# rev0_1.net
KiCad netlist of a schematic drawn in EAGLE
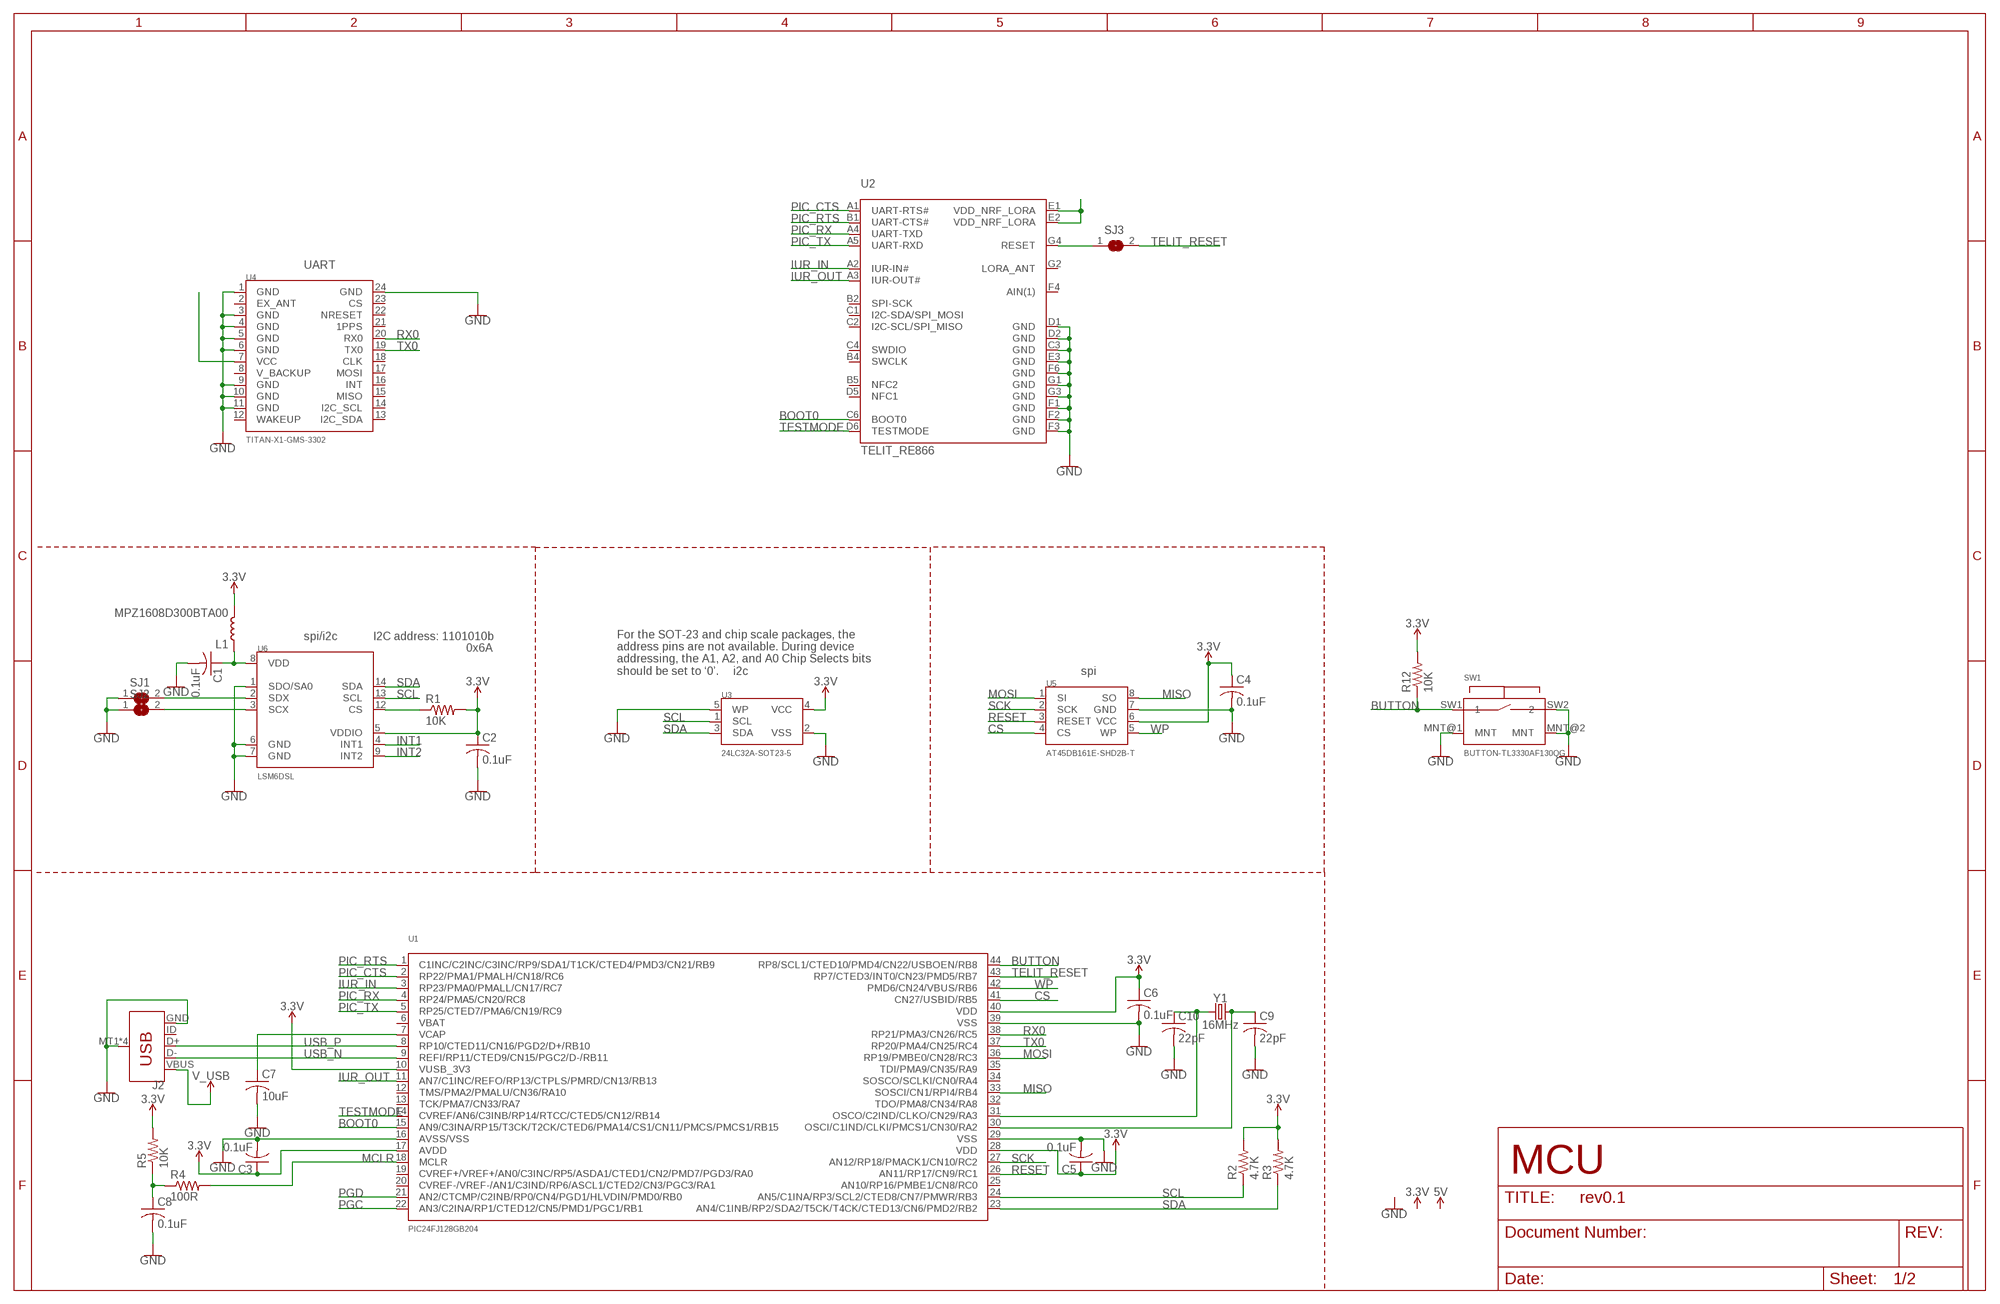
[diagram p0: schematic, sheet 1]
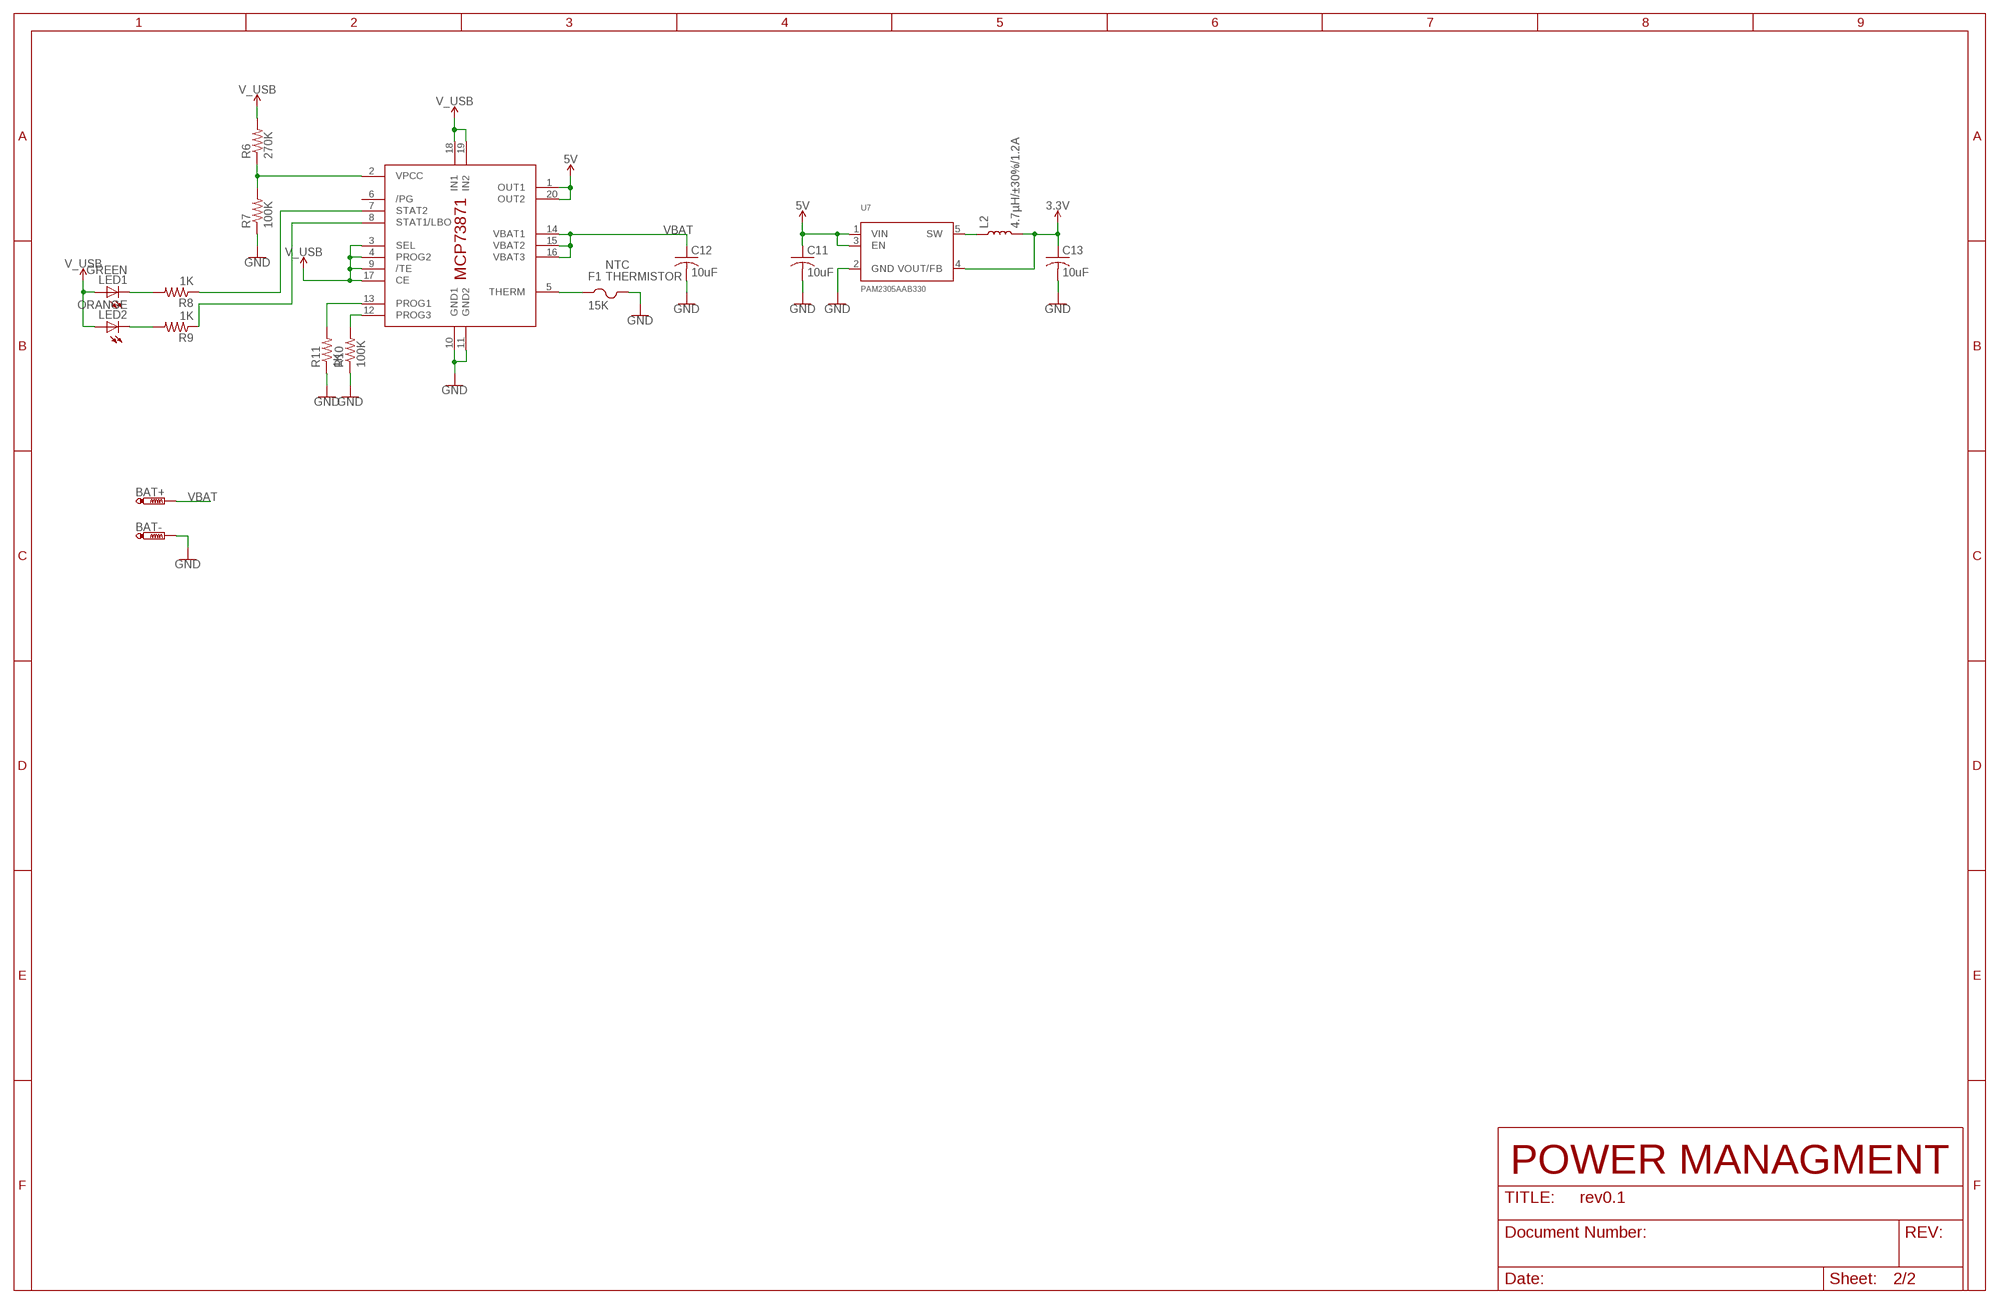
[diagram p1: schematic, sheet 2]

(export (version "E")
  (design (tool "Eeschema 10.0.6"))
  (components
    (comp (ref "C1")
      (value "0.1uF")
      (footprint "eagle-import:C0402")
      (libsource (lib "eagle-import") (part "C-USC0402"))
    )
    (comp (ref "C2")
      (value "0.1uF")
      (footprint "eagle-import:C0402")
      (libsource (lib "eagle-import") (part "C-USC0402"))
    )
    (comp (ref "C3")
      (value "0.1uF")
      (footprint "eagle-import:C0402")
      (libsource (lib "eagle-import") (part "C-USC0402"))
    )
    (comp (ref "C4")
      (value "0.1uF")
      (footprint "eagle-import:C0402")
      (libsource (lib "eagle-import") (part "C-USC0402"))
    )
    (comp (ref "C5")
      (value "0.1uF")
      (footprint "eagle-import:C0402")
      (libsource (lib "eagle-import") (part "C-USC0402"))
    )
    (comp (ref "C6")
      (value "0.1uF")
      (footprint "eagle-import:C0402")
      (libsource (lib "eagle-import") (part "C-USC0402"))
    )
    (comp (ref "C7")
      (value "10uF")
      (footprint "eagle-import:C0603")
      (libsource (lib "eagle-import") (part "C-USC0603"))
    )
    (comp (ref "C8")
      (value "0.1uF")
      (footprint "eagle-import:C0402")
      (libsource (lib "eagle-import") (part "C-USC0402"))
    )
    (comp (ref "C9")
      (value "22pF")
      (footprint "eagle-import:C0402")
      (libsource (lib "eagle-import") (part "C-USC0402"))
    )
    (comp (ref "C10")
      (value "22pF")
      (footprint "eagle-import:C0402")
      (libsource (lib "eagle-import") (part "C-USC0402"))
    )
    (comp (ref "J2")
      (value "USB_MICRO-B_SMT")
      (footprint "eagle-import:USB-MICROB")
      (libsource (lib "eagle-import") (part "USB_MICRO-B_SMT"))
    )
    (comp (ref "L1")
      (value "MPZ1608D300BTA00")
      (footprint "eagle-import:0402")
      (libsource (lib "eagle-import") (part "INDUCTOR-0402-3.9NH"))
    )
    (comp (ref "R1")
      (value "10K")
      (footprint "eagle-import:R0402")
      (libsource (lib "eagle-import") (part "R-US_R0402"))
    )
    (comp (ref "R2")
      (value "4.7K")
      (footprint "eagle-import:R0402")
      (libsource (lib "eagle-import") (part "R-US_R0402"))
    )
    (comp (ref "R3")
      (value "4.7K")
      (footprint "eagle-import:R0402")
      (libsource (lib "eagle-import") (part "R-US_R0402"))
    )
    (comp (ref "R4")
      (value "100R")
      (footprint "eagle-import:R0402")
      (libsource (lib "eagle-import") (part "R-US_R0402"))
    )
    (comp (ref "R5")
      (value "10K")
      (footprint "eagle-import:R0402")
      (libsource (lib "eagle-import") (part "R-US_R0402"))
    )
    (comp (ref "R12")
      (value "10K")
      (footprint "eagle-import:R0402")
      (libsource (lib "eagle-import") (part "R-US_R0402"))
    )
    (comp (ref "SJ1") (value "SJ") (footprint "eagle-import:SJ") (libsource (lib "eagle-import") (part "SJ")))
    (comp (ref "SJ2") (value "SJ") (footprint "eagle-import:SJ") (libsource (lib "eagle-import") (part "SJ")))
    (comp (ref "SJ3") (value "SJ") (footprint "eagle-import:SJ") (libsource (lib "eagle-import") (part "SJ")))
    (comp (ref "SW1")
      (value "BUTTON-TL3330AF130QG")
      (footprint "eagle-import:BUTTON-TL3330AF130QG")
      (libsource (lib "eagle-import") (part "BUTTON-TL3330AF130QG"))
    )
    (comp (ref "U1")
      (value "PIC24FJ128GB204")
      (footprint "eagle-import:PIC24FJ128GB204")
      (libsource (lib "eagle-import") (part "PIC24FJ128GB204"))
    )
    (comp (ref "U2")
      (value "TELIT_RE866")
      (footprint "eagle-import:TELIT_RE866")
      (libsource (lib "eagle-import") (part "TELIT_RE866"))
    )
    (comp (ref "U3")
      (value "24LC32A-SOT23-5")
      (footprint "eagle-import:24LC32A-SOT23-5")
      (libsource (lib "eagle-import") (part "24LC32A-SOT23-5"))
    )
    (comp (ref "U4")
      (value "TITAN-X1-GMS-3302")
      (footprint "eagle-import:TITAN-X1-GMS-3302")
      (libsource (lib "eagle-import") (part "TITAN-X1-GMS-3302"))
    )
    (comp (ref "U5")
      (value "AT45DB161E-SHD2B-T")
      (footprint "eagle-import:AT45DB161E-SHD2B-T")
      (libsource (lib "eagle-import") (part "AT45DB161E-SHD2B-T"))
    )
    (comp (ref "U6")
      (value "LSM6DSL")
      (footprint "eagle-import:LSM6DSL")
      (fields (field (name "SPICEPREFIX") "X"))
      (libsource (lib "eagle-import") (part "LSM6DSL"))
    )
    (comp (ref "Y1")
      (value "16MHz")
      (footprint "eagle-import:CRYSTAL-SMD-5X3.2-4PAD")
      (libsource (lib "eagle-import") (part "CRYSTAL-16MHZSMD-5X3.2"))
    )
    (comp (ref "BAT+")
      (value "PTR1B2,54")
      (footprint "eagle-import:B2,54")
      (libsource (lib "eagle-import") (part "PTR1B2,54"))
    )
    (comp (ref "BAT-")
      (value "PTR1B2,54")
      (footprint "eagle-import:B2,54")
      (libsource (lib "eagle-import") (part "PTR1B2,54"))
    )
    (comp (ref "C11")
      (value "10uF")
      (footprint "eagle-import:C0805")
      (libsource (lib "eagle-import") (part "C-USC0805"))
    )
    (comp (ref "C12")
      (value "10uF")
      (footprint "eagle-import:C0603")
      (libsource (lib "eagle-import") (part "C-USC0603"))
    )
    (comp (ref "C13")
      (value "10uF")
      (footprint "eagle-import:C0805")
      (libsource (lib "eagle-import") (part "C-USC0805"))
    )
    (comp (ref "F1")
      (value "15K")
      (footprint "eagle-import:R1206")
      (libsource (lib "eagle-import") (part "PTCFUSE-1206"))
    )
    (comp (ref "IC2")
      (value "MCP73871")
      (footprint "eagle-import:QFN20")
      (libsource (lib "eagle-import") (part "MCP73871"))
    )
    (comp (ref "L2")
      (value "4.7µH/±30%/1.2A")
      (footprint "eagle-import:INDUCTOR_4.7UH")
      (libsource (lib "eagle-import") (part "INDUCTOR-CDRH-4.7UH"))
    )
    (comp (ref "LED1")
      (value "GREEN")
      (footprint "eagle-import:CHIP-LED0603")
      (libsource (lib "eagle-import") (part "LEDCHIP-LED0603"))
    )
    (comp (ref "LED2")
      (value "ORANGE")
      (footprint "eagle-import:CHIP-LED0603")
      (libsource (lib "eagle-import") (part "LEDCHIP-LED0603"))
    )
    (comp (ref "R6")
      (value "270K")
      (footprint "eagle-import:R0402")
      (libsource (lib "eagle-import") (part "R-US_R0402"))
    )
    (comp (ref "R7")
      (value "100K")
      (footprint "eagle-import:R0402")
      (libsource (lib "eagle-import") (part "R-US_R0402"))
    )
    (comp (ref "R8")
      (value "1K")
      (footprint "eagle-import:R0402")
      (libsource (lib "eagle-import") (part "R-US_R0402"))
    )
    (comp (ref "R9")
      (value "1K")
      (footprint "eagle-import:R0402")
      (libsource (lib "eagle-import") (part "R-US_R0402"))
    )
    (comp (ref "R10")
      (value "100K")
      (footprint "eagle-import:R0402")
      (libsource (lib "eagle-import") (part "R-US_R0402"))
    )
    (comp (ref "R11")
      (value "1K")
      (footprint "eagle-import:R0402")
      (libsource (lib "eagle-import") (part "R-US_R0402"))
    )
    (comp (ref "U7")
      (value "PAM2305AAB330")
      (footprint "eagle-import:PAM2305AAB330")
      (libsource (lib "eagle-import") (part "PAM2305AAB330"))
    )
  )
  (nets
    (net (code "1") (name "3.3V") (class "Default")
      (node (ref "C13") (pin "1") (pinfunction "1_1") (pintype "passive"))
      (node (ref "C2") (pin "1") (pinfunction "1_1") (pintype "passive"))
      (node (ref "C3") (pin "1") (pinfunction "1_1") (pintype "passive"))
      (node (ref "C4") (pin "1") (pinfunction "1_1") (pintype "passive"))
      (node (ref "C5") (pin "1") (pinfunction "1_1") (pintype "passive"))
      (node (ref "C6") (pin "1") (pinfunction "1_1") (pintype "passive"))
      (node (ref "L1") (pin "2") (pinfunction "2_2") (pintype "passive"))
      (node (ref "L2") (pin "P$2") (pinfunction "2_P$2") (pintype "passive"))
      (node (ref "R1") (pin "2") (pinfunction "2_2") (pintype "passive"))
      (node (ref "R12") (pin "2") (pinfunction "2_2") (pintype "passive"))
      (node (ref "R2") (pin "2") (pinfunction "2_2") (pintype "passive"))
      (node (ref "R3") (pin "2") (pinfunction "2_2") (pintype "passive"))
      (node (ref "R5") (pin "2") (pinfunction "2_2") (pintype "passive"))
      (node (ref "U1") (pin "10") (pinfunction "VUSB_3V3_10") (pintype "bidirectional"))
      (node (ref "U1") (pin "17") (pinfunction "AVDD_17") (pintype "bidirectional"))
      (node (ref "U1") (pin "28") (pinfunction "VDD_28") (pintype "bidirectional"))
      (node (ref "U1") (pin "40") (pinfunction "VDD_40") (pintype "bidirectional"))
      (node (ref "U3") (pin "4") (pinfunction "VCC_4") (pintype "bidirectional"))
      (node (ref "U5") (pin "6") (pinfunction "VCC_6") (pintype "bidirectional"))
      (node (ref "U6") (pin "5") (pinfunction "VDDIO_5") (pintype "bidirectional"))
      (node (ref "U7") (pin "4") (pinfunction "VOUT/FB_4") (pintype "bidirectional"))
    )
    (net (code "2") (name "5V") (class "Default")
      (node (ref "C11") (pin "1") (pinfunction "1_1") (pintype "passive"))
      (node (ref "IC2") (pin "1") (pinfunction "OUT1_1") (pintype "output"))
      (node (ref "IC2") (pin "20") (pinfunction "OUT2_20") (pintype "output"))
      (node (ref "U7") (pin "1") (pinfunction "VIN_1") (pintype "bidirectional"))
      (node (ref "U7") (pin "3") (pinfunction "EN_3") (pintype "bidirectional"))
    )
    (net (code "3") (name "BOOT0") (class "Default")
      (node (ref "U1") (pin "15") (pinfunction "AN9/C3INA/RP15/T3CK/T2CK/CTED6/PMA14/CS1/CN11/PMCS/PMCS1/RB15_15") (pintype "bidirectional"))
      (node (ref "U2") (pin "C6") (pinfunction "BOOT0_C6") (pintype "bidirectional"))
    )
    (net (code "4") (name "BUTTON") (class "Default")
      (node (ref "R12") (pin "1") (pinfunction "1_1") (pintype "passive"))
      (node (ref "SW1") (pin "SW1") (pinfunction "1_SW1") (pintype "bidirectional"))
      (node (ref "U1") (pin "44") (pinfunction "RP8/SCL1/CTED10/PMD4/CN22/USBOEN/RB8_44") (pintype "bidirectional"))
    )
    (net (code "5") (name "CS") (class "Default")
      (node (ref "U1") (pin "41") (pinfunction "CN27/USBID/RB5_41") (pintype "bidirectional"))
      (node (ref "U5") (pin "4") (pinfunction "CS_4") (pintype "bidirectional"))
    )
    (net (code "6") (name "GND") (class "Default")
      (node (ref "BAT-") (pin "TP") (pinfunction "TP_TP") (pintype "input"))
      (node (ref "C1") (pin "2") (pinfunction "2_2") (pintype "passive"))
      (node (ref "C10") (pin "2") (pinfunction "2_2") (pintype "passive"))
      (node (ref "C11") (pin "2") (pinfunction "2_2") (pintype "passive"))
      (node (ref "C12") (pin "2") (pinfunction "2_2") (pintype "passive"))
      (node (ref "C13") (pin "2") (pinfunction "2_2") (pintype "passive"))
      (node (ref "C2") (pin "2") (pinfunction "2_2") (pintype "passive"))
      (node (ref "C3") (pin "2") (pinfunction "2_2") (pintype "passive"))
      (node (ref "C4") (pin "2") (pinfunction "2_2") (pintype "passive"))
      (node (ref "C5") (pin "2") (pinfunction "2_2") (pintype "passive"))
      (node (ref "C6") (pin "2") (pinfunction "2_2") (pintype "passive"))
      (node (ref "C7") (pin "2") (pinfunction "2_2") (pintype "passive"))
      (node (ref "C8") (pin "2") (pinfunction "2_2") (pintype "passive"))
      (node (ref "C9") (pin "2") (pinfunction "2_2") (pintype "passive"))
      (node (ref "F1") (pin "2") (pinfunction "2_2") (pintype "passive"))
      (node (ref "IC2") (pin "10") (pinfunction "GND1_10") (pintype "power_in"))
      (node (ref "IC2") (pin "11") (pinfunction "GND2_11") (pintype "power_in"))
      (node (ref "J2") (pin "GND") (pinfunction "GND_GND") (pintype "power_in"))
      (node (ref "J2") (pin "MT1") (pinfunction "SHIELD_MT1") (pintype "bidirectional"))
      (node (ref "J2") (pin "MT2") (pinfunction "SHIELD_MT2") (pintype "bidirectional"))
      (node (ref "J2") (pin "P$1") (pinfunction "SHIELD_P$1") (pintype "bidirectional"))
      (node (ref "J2") (pin "P$2") (pinfunction "SHIELD_P$2") (pintype "bidirectional"))
      (node (ref "R10") (pin "1") (pinfunction "1_1") (pintype "passive"))
      (node (ref "R11") (pin "1") (pinfunction "1_1") (pintype "passive"))
      (node (ref "R7") (pin "1") (pinfunction "1_1") (pintype "passive"))
      (node (ref "SJ1") (pin "1") (pinfunction "1_1") (pintype "passive"))
      (node (ref "SJ2") (pin "1") (pinfunction "1_1") (pintype "passive"))
      (node (ref "SW1") (pin "MNT@1") (pinfunction "MNT_MNT@1") (pintype "bidirectional"))
      (node (ref "SW1") (pin "MNT@2") (pinfunction "MNT_MNT@2") (pintype "bidirectional"))
      (node (ref "SW1") (pin "SW2") (pinfunction "2_SW2") (pintype "bidirectional"))
      (node (ref "U1") (pin "16") (pinfunction "AVSS/VSS_16") (pintype "bidirectional"))
      (node (ref "U1") (pin "29") (pinfunction "VSS_29") (pintype "bidirectional"))
      (node (ref "U1") (pin "39") (pinfunction "VSS_39") (pintype "bidirectional"))
      (node (ref "U2") (pin "C3") (pinfunction "GND_C3") (pintype "bidirectional"))
      (node (ref "U2") (pin "D1") (pinfunction "GND_D1") (pintype "bidirectional"))
      (node (ref "U2") (pin "D2") (pinfunction "GND_D2") (pintype "bidirectional"))
      (node (ref "U2") (pin "E3") (pinfunction "GND_E3") (pintype "bidirectional"))
      (node (ref "U2") (pin "F1") (pinfunction "GND_F1") (pintype "bidirectional"))
      (node (ref "U2") (pin "F2") (pinfunction "GND_F2") (pintype "bidirectional"))
      (node (ref "U2") (pin "F3") (pinfunction "GND_F3") (pintype "bidirectional"))
      (node (ref "U2") (pin "F6") (pinfunction "GND_F6") (pintype "bidirectional"))
      (node (ref "U2") (pin "G1") (pinfunction "GND_G1") (pintype "bidirectional"))
      (node (ref "U2") (pin "G3") (pinfunction "GND_G3") (pintype "bidirectional"))
      (node (ref "U3") (pin "2") (pinfunction "VSS_2") (pintype "bidirectional"))
      (node (ref "U3") (pin "5") (pinfunction "WP_5") (pintype "bidirectional"))
      (node (ref "U4") (pin "1") (pinfunction "GND_1") (pintype "bidirectional"))
      (node (ref "U4") (pin "10") (pinfunction "GND_10") (pintype "bidirectional"))
      (node (ref "U4") (pin "11") (pinfunction "GND_11") (pintype "bidirectional"))
      (node (ref "U4") (pin "24") (pinfunction "GND_24") (pintype "bidirectional"))
      (node (ref "U4") (pin "3") (pinfunction "GND_3") (pintype "bidirectional"))
      (node (ref "U4") (pin "4") (pinfunction "GND_4") (pintype "bidirectional"))
      (node (ref "U4") (pin "5") (pinfunction "GND_5") (pintype "bidirectional"))
      (node (ref "U4") (pin "6") (pinfunction "GND_6") (pintype "bidirectional"))
      (node (ref "U4") (pin "9") (pinfunction "GND_9") (pintype "bidirectional"))
      (node (ref "U5") (pin "7") (pinfunction "GND_7") (pintype "bidirectional"))
      (node (ref "U6") (pin "1") (pinfunction "SDO/SA0_1") (pintype "bidirectional"))
      (node (ref "U6") (pin "6") (pinfunction "GND_6") (pintype "bidirectional"))
      (node (ref "U6") (pin "7") (pinfunction "GND_7") (pintype "bidirectional"))
      (node (ref "U7") (pin "2") (pinfunction "GND_2") (pintype "bidirectional"))
    )
    (net (code "7") (name "INT1") (class "Default")
      (node (ref "U6") (pin "4") (pinfunction "INT1_4") (pintype "bidirectional"))
    )
    (net (code "8") (name "INT2") (class "Default")
      (node (ref "U6") (pin "9") (pinfunction "INT2_9") (pintype "bidirectional"))
    )
    (net (code "9") (name "IUR_IN") (class "Default")
      (node (ref "U1") (pin "3") (pinfunction "RP23/PMA0/PMALL/CN17/RC7_3") (pintype "bidirectional"))
      (node (ref "U2") (pin "A2") (pinfunction "IUR-IN#_A2") (pintype "bidirectional"))
    )
    (net (code "10") (name "IUR_OUT") (class "Default")
      (node (ref "U1") (pin "11") (pinfunction "AN7/C1INC/REFO/RP13/CTPLS/PMRD/CN13/RB13_11") (pintype "bidirectional"))
      (node (ref "U2") (pin "A3") (pinfunction "IUR-OUT#_A3") (pintype "bidirectional"))
    )
    (net (code "11") (name "MCLR") (class "Default")
      (node (ref "R4") (pin "2") (pinfunction "2_2") (pintype "passive"))
      (node (ref "U1") (pin "18") (pinfunction "MCLR_18") (pintype "bidirectional"))
    )
    (net (code "12") (name "MISO") (class "Default")
      (node (ref "U1") (pin "33") (pinfunction "SOSCI/CN1/RPI4/RB4_33") (pintype "bidirectional"))
      (node (ref "U5") (pin "8") (pinfunction "SO_8") (pintype "bidirectional"))
    )
    (net (code "13") (name "MOSI") (class "Default")
      (node (ref "U1") (pin "36") (pinfunction "RP19/PMBE0/CN28/RC3_36") (pintype "bidirectional"))
      (node (ref "U5") (pin "1") (pinfunction "SI_1") (pintype "bidirectional"))
    )
    (net (code "14") (name "Net-(C8-Pad1)") (class "Default")
      (node (ref "C8") (pin "1") (pinfunction "1_1") (pintype "passive"))
      (node (ref "R4") (pin "1") (pinfunction "1_1") (pintype "passive"))
      (node (ref "R5") (pin "1") (pinfunction "1_1") (pintype "passive"))
    )
    (net (code "15") (name "Net-(IC2-PROG1)") (class "Default")
      (node (ref "IC2") (pin "13") (pinfunction "PROG1_13") (pintype "input"))
      (node (ref "R11") (pin "2") (pinfunction "2_2") (pintype "passive"))
    )
    (net (code "16") (name "Net-(IC2-PROG3)") (class "Default")
      (node (ref "IC2") (pin "12") (pinfunction "PROG3_12") (pintype "input"))
      (node (ref "R10") (pin "2") (pinfunction "2_2") (pintype "passive"))
    )
    (net (code "17") (name "Net-(IC2-STAT1{slash}LBO)") (class "Default")
      (node (ref "IC2") (pin "8") (pinfunction "STAT1/LBO_8") (pintype "output"))
      (node (ref "R9") (pin "1") (pinfunction "1_1") (pintype "passive"))
    )
    (net (code "18") (name "Net-(IC2-STAT2)") (class "Default")
      (node (ref "IC2") (pin "7") (pinfunction "STAT2_7") (pintype "output"))
      (node (ref "R8") (pin "1") (pinfunction "1_1") (pintype "passive"))
    )
    (net (code "19") (name "Net-(IC2-THERM)") (class "Default")
      (node (ref "F1") (pin "1") (pinfunction "1_1") (pintype "passive"))
      (node (ref "IC2") (pin "5") (pinfunction "THERM_5") (pintype "input"))
    )
    (net (code "20") (name "Net-(IC2-VPCC)") (class "Default")
      (node (ref "IC2") (pin "2") (pinfunction "VPCC_2") (pintype "input"))
      (node (ref "R6") (pin "1") (pinfunction "1_1") (pintype "passive"))
      (node (ref "R7") (pin "2") (pinfunction "2_2") (pintype "passive"))
    )
    (net (code "21") (name "Net-(L2-1)") (class "Default")
      (node (ref "L2") (pin "P$1") (pinfunction "1_P$1") (pintype "passive"))
      (node (ref "U7") (pin "5") (pinfunction "SW_5") (pintype "bidirectional"))
    )
    (net (code "22") (name "Net-(LED1-PadC)") (class "Default")
      (node (ref "LED1") (pin "C") (pinfunction "C_C") (pintype "passive"))
      (node (ref "R8") (pin "2") (pinfunction "2_2") (pintype "passive"))
    )
    (net (code "23") (name "Net-(LED2-PadC)") (class "Default")
      (node (ref "LED2") (pin "C") (pinfunction "C_C") (pintype "passive"))
      (node (ref "R9") (pin "2") (pinfunction "2_2") (pintype "passive"))
    )
    (net (code "24") (name "Net-(U1-OSCI{slash}C1IND{slash}CLKI{slash}PMCS1{slash}CN30{slash}RA2)") (class "Default")
      (node (ref "C9") (pin "1") (pinfunction "1_1") (pintype "passive"))
      (node (ref "U1") (pin "30") (pinfunction "OSCI/C1IND/CLKI/PMCS1/CN30/RA2_30") (pintype "bidirectional"))
      (node (ref "Y1") (pin "3") (pinfunction "2_3") (pintype "passive"))
    )
    (net (code "25") (name "Net-(U1-OSCO{slash}C2IND{slash}CLKO{slash}CN29{slash}RA3)") (class "Default")
      (node (ref "C10") (pin "1") (pinfunction "1_1") (pintype "passive"))
      (node (ref "U1") (pin "31") (pinfunction "OSCO/C2IND/CLKO/CN29/RA3_31") (pintype "bidirectional"))
      (node (ref "Y1") (pin "1") (pinfunction "1_1") (pintype "passive"))
    )
    (net (code "26") (name "Net-(U1-VCAP)") (class "Default")
      (node (ref "C7") (pin "1") (pinfunction "1_1") (pintype "passive"))
      (node (ref "U1") (pin "7") (pinfunction "VCAP_7") (pintype "bidirectional"))
    )
    (net (code "27") (name "Net-(U2-RESET)") (class "Default")
      (node (ref "SJ3") (pin "1") (pinfunction "1_1") (pintype "passive"))
      (node (ref "U2") (pin "G4") (pinfunction "RESET_G4") (pintype "bidirectional"))
    )
    (net (code "28") (name "Net-(U2-VDD_NRF_LORA-PadE1)") (class "Default")
      (node (ref "U2") (pin "E1") (pinfunction "VDD_NRF_LORA_E1") (pintype "bidirectional"))
      (node (ref "U2") (pin "E2") (pinfunction "VDD_NRF_LORA_E2") (pintype "bidirectional"))
    )
    (net (code "29") (name "Net-(U6-CS)") (class "Default")
      (node (ref "R1") (pin "1") (pinfunction "1_1") (pintype "passive"))
      (node (ref "U6") (pin "12") (pinfunction "CS_12") (pintype "bidirectional"))
    )
    (net (code "30") (name "Net-(U6-SCX)") (class "Default")
      (node (ref "SJ2") (pin "2") (pinfunction "2_2") (pintype "passive"))
      (node (ref "U6") (pin "3") (pinfunction "SCX_3") (pintype "bidirectional"))
    )
    (net (code "31") (name "Net-(U6-SDX)") (class "Default")
      (node (ref "SJ1") (pin "2") (pinfunction "2_2") (pintype "passive"))
      (node (ref "U6") (pin "2") (pinfunction "SDX_2") (pintype "bidirectional"))
    )
    (net (code "32") (name "Net-(U6-VDD)") (class "Default")
      (node (ref "C1") (pin "1") (pinfunction "1_1") (pintype "passive"))
      (node (ref "L1") (pin "1") (pinfunction "1_1") (pintype "passive"))
      (node (ref "U6") (pin "8") (pinfunction "VDD_8") (pintype "bidirectional"))
    )
    (net (code "33") (name "PGC") (class "Default")
      (node (ref "U1") (pin "22") (pinfunction "AN3/C2INA/RP1/CTED12/CN5/PMD1/PGC1/RB1_22") (pintype "bidirectional"))
    )
    (net (code "34") (name "PGD") (class "Default")
      (node (ref "U1") (pin "21") (pinfunction "AN2/CTCMP/C2INB/RP0/CN4/PGD1/HLVDIN/PMD0/RB0_21") (pintype "bidirectional"))
    )
    (net (code "35") (name "PIC_CTS") (class "Default")
      (node (ref "U1") (pin "2") (pinfunction "RP22/PMA1/PMALH/CN18/RC6_2") (pintype "bidirectional"))
      (node (ref "U2") (pin "A1") (pinfunction "UART-RTS#_A1") (pintype "bidirectional"))
    )
    (net (code "36") (name "PIC_RTS") (class "Default")
      (node (ref "U1") (pin "1") (pinfunction "C1INC/C2INC/C3INC/RP9/SDA1/T1CK/CTED4/PMD3/CN21/RB9_1") (pintype "bidirectional"))
      (node (ref "U2") (pin "B1") (pinfunction "UART-CTS#_B1") (pintype "bidirectional"))
    )
    (net (code "37") (name "PIC_RX") (class "Default")
      (node (ref "U1") (pin "4") (pinfunction "RP24/PMA5/CN20/RC8_4") (pintype "bidirectional"))
      (node (ref "U2") (pin "A4") (pinfunction "UART-TXD_A4") (pintype "bidirectional"))
    )
    (net (code "38") (name "PIC_TX") (class "Default")
      (node (ref "U1") (pin "5") (pinfunction "RP25/CTED7/PMA6/CN19/RC9_5") (pintype "bidirectional"))
      (node (ref "U2") (pin "A5") (pinfunction "UART-RXD_A5") (pintype "bidirectional"))
    )
    (net (code "39") (name "RESET") (class "Default")
      (node (ref "U1") (pin "26") (pinfunction "AN11/RP17/CN9/RC1_26") (pintype "bidirectional"))
      (node (ref "U5") (pin "3") (pinfunction "RESET_3") (pintype "bidirectional"))
    )
    (net (code "40") (name "RX0") (class "Default")
      (node (ref "U1") (pin "38") (pinfunction "RP21/PMA3/CN26/RC5_38") (pintype "bidirectional"))
      (node (ref "U4") (pin "20") (pinfunction "RX0_20") (pintype "bidirectional"))
    )
    (net (code "41") (name "SCK") (class "Default")
      (node (ref "U1") (pin "27") (pinfunction "AN12/RP18/PMACK1/CN10/RC2_27") (pintype "bidirectional"))
      (node (ref "U5") (pin "2") (pinfunction "SCK_2") (pintype "bidirectional"))
    )
    (net (code "42") (name "SCL") (class "Default")
      (node (ref "R2") (pin "1") (pinfunction "1_1") (pintype "passive"))
      (node (ref "U1") (pin "24") (pinfunction "AN5/C1INA/RP3/SCL2/CTED8/CN7/PMWR/RB3_24") (pintype "bidirectional"))
      (node (ref "U3") (pin "1") (pinfunction "SCL_1") (pintype "bidirectional"))
      (node (ref "U6") (pin "13") (pinfunction "SCL_13") (pintype "bidirectional"))
    )
    (net (code "43") (name "SDA") (class "Default")
      (node (ref "R3") (pin "1") (pinfunction "1_1") (pintype "passive"))
      (node (ref "U1") (pin "23") (pinfunction "AN4/C1INB/RP2/SDA2/T5CK/T4CK/CTED13/CN6/PMD2/RB2_23") (pintype "bidirectional"))
      (node (ref "U3") (pin "3") (pinfunction "SDA_3") (pintype "bidirectional"))
      (node (ref "U6") (pin "14") (pinfunction "SDA_14") (pintype "bidirectional"))
    )
    (net (code "44") (name "TELIT_RESET") (class "Default")
      (node (ref "SJ3") (pin "2") (pinfunction "2_2") (pintype "passive"))
      (node (ref "U1") (pin "43") (pinfunction "RP7/CTED3/INT0/CN23/PMD5/RB7_43") (pintype "bidirectional"))
    )
    (net (code "45") (name "TESTMODE") (class "Default")
      (node (ref "U1") (pin "14") (pinfunction "CVREF/AN6/C3INB/RP14/RTCC/CTED5/CN12/RB14_14") (pintype "bidirectional"))
      (node (ref "U2") (pin "D6") (pinfunction "TESTMODE_D6") (pintype "bidirectional"))
    )
    (net (code "46") (name "TX0") (class "Default")
      (node (ref "U1") (pin "37") (pinfunction "RP20/PMA4/CN25/RC4_37") (pintype "bidirectional"))
      (node (ref "U4") (pin "19") (pinfunction "TX0_19") (pintype "bidirectional"))
    )
    (net (code "47") (name "USB_N") (class "Default")
      (node (ref "J2") (pin "D-") (pinfunction "D-_D-") (pintype "bidirectional"))
      (node (ref "U1") (pin "9") (pinfunction "REFI/RP11/CTED9/CN15/PGC2/D-/RB11_9") (pintype "bidirectional"))
    )
    (net (code "48") (name "USB_P") (class "Default")
      (node (ref "J2") (pin "D+") (pinfunction "D+_D+") (pintype "bidirectional"))
      (node (ref "U1") (pin "8") (pinfunction "RP10/CTED11/CN16/PGD2/D+/RB10_8") (pintype "bidirectional"))
    )
    (net (code "49") (name "VBAT") (class "Default")
      (node (ref "BAT+") (pin "TP") (pinfunction "TP_TP") (pintype "input"))
      (node (ref "C12") (pin "1") (pinfunction "1_1") (pintype "passive"))
      (node (ref "IC2") (pin "14") (pinfunction "VBAT1_14") (pintype "output"))
      (node (ref "IC2") (pin "15") (pinfunction "VBAT2_15") (pintype "output"))
      (node (ref "IC2") (pin "16") (pinfunction "VBAT3_16") (pintype "output"))
    )
    (net (code "50") (name "V_USB") (class "Default")
      (node (ref "IC2") (pin "17") (pinfunction "CE_17") (pintype "input"))
      (node (ref "IC2") (pin "18") (pinfunction "IN1_18") (pintype "input"))
      (node (ref "IC2") (pin "19") (pinfunction "IN2_19") (pintype "input"))
      (node (ref "IC2") (pin "3") (pinfunction "SEL_3") (pintype "input"))
      (node (ref "IC2") (pin "4") (pinfunction "PROG2_4") (pintype "input"))
      (node (ref "IC2") (pin "9") (pinfunction "/TE_9") (pintype "input"))
      (node (ref "J2") (pin "VBUS") (pinfunction "VBUS_VBUS") (pintype "power_in"))
      (node (ref "LED1") (pin "A") (pinfunction "A_A") (pintype "passive"))
      (node (ref "LED2") (pin "A") (pinfunction "A_A") (pintype "passive"))
      (node (ref "R6") (pin "2") (pinfunction "2_2") (pintype "passive"))
    )
    (net (code "51") (name "WP") (class "Default")
      (node (ref "U1") (pin "42") (pinfunction "PMD6/CN24/VBUS/RB6_42") (pintype "bidirectional"))
      (node (ref "U5") (pin "5") (pinfunction "WP_5") (pintype "bidirectional"))
    )
    (net (code "52") (name "unconnected-(IC2-{slash}PG-Pad6)") (class "Default")
      (node (ref "IC2") (pin "6") (pinfunction "/PG_6") (pintype "output"))
    )
    (net (code "53") (name "unconnected-(J2-PadID)") (class "Default")
      (node (ref "J2") (pin "ID") (pinfunction "ID_ID") (pintype "bidirectional"))
    )
    (net (code "54") (name "unconnected-(U1-AN10{slash}RP16{slash}PMBE1{slash}CN8{slash}RC0-Pad25)") (class "Default")
      (node (ref "U1") (pin "25") (pinfunction "AN10/RP16/PMBE1/CN8/RC0_25") (pintype "bidirectional"))
    )
    (net (code "55") (name "unconnected-(U1-CVREF+{slash}VREF+{slash}AN0{slash}C3INC{slash}RP5{slash}ASDA1{slash}CTED1{slash}CN2{slash}PMD7{slash}PGD3{slash}RA0-Pad19)") (class "Default")
      (node (ref "U1") (pin "19") (pinfunction "CVREF+/VREF+/AN0/C3INC/RP5/ASDA1/CTED1/CN2/PMD7/PGD3/RA0_19") (pintype "bidirectional"))
    )
    (net (code "56") (name "unconnected-(U1-CVREF-{slash}VREF-{slash}AN1{slash}C3IND{slash}RP6{slash}ASCL1{slash}CTED2{slash}CN3{slash}PGC3{slash}RA1-Pad20)") (class "Default")
      (node (ref "U1") (pin "20") (pinfunction "CVREF-/VREF-/AN1/C3IND/RP6/ASCL1/CTED2/CN3/PGC3/RA1_20") (pintype "bidirectional"))
    )
    (net (code "57") (name "unconnected-(U1-SOSCO{slash}SCLKI{slash}CN0{slash}RA4-Pad34)") (class "Default")
      (node (ref "U1") (pin "34") (pinfunction "SOSCO/SCLKI/CN0/RA4_34") (pintype "bidirectional"))
    )
    (net (code "58") (name "unconnected-(U1-TCK{slash}PMA7{slash}CN33{slash}RA7-Pad13)") (class "Default")
      (node (ref "U1") (pin "13") (pinfunction "TCK/PMA7/CN33/RA7_13") (pintype "bidirectional"))
    )
    (net (code "59") (name "unconnected-(U1-TDI{slash}PMA9{slash}CN35{slash}RA9-Pad35)") (class "Default")
      (node (ref "U1") (pin "35") (pinfunction "TDI/PMA9/CN35/RA9_35") (pintype "bidirectional"))
    )
    (net (code "60") (name "unconnected-(U1-TDO{slash}PMA8{slash}CN34{slash}RA8-Pad32)") (class "Default")
      (node (ref "U1") (pin "32") (pinfunction "TDO/PMA8/CN34/RA8_32") (pintype "bidirectional"))
    )
    (net (code "61") (name "unconnected-(U1-TMS{slash}PMA2{slash}PMALU{slash}CN36{slash}RA10-Pad12)") (class "Default")
      (node (ref "U1") (pin "12") (pinfunction "TMS/PMA2/PMALU/CN36/RA10_12") (pintype "bidirectional"))
    )
    (net (code "62") (name "unconnected-(U1-VBAT-Pad6)") (class "Default")
      (node (ref "U1") (pin "6") (pinfunction "VBAT_6") (pintype "bidirectional"))
    )
    (net (code "63") (name "unconnected-(U2-AIN(1)-PadF4)") (class "Default")
      (node (ref "U2") (pin "F4") (pinfunction "AIN(1)_F4") (pintype "bidirectional"))
    )
    (net (code "64") (name "unconnected-(U2-I2C-SCL{slash}SPI_MISO-PadC2)") (class "Default")
      (node (ref "U2") (pin "C2") (pinfunction "I2C-SCL/SPI_MISO_C2") (pintype "bidirectional"))
    )
    (net (code "65") (name "unconnected-(U2-I2C-SDA{slash}SPI_MOSI-PadC1)") (class "Default")
      (node (ref "U2") (pin "C1") (pinfunction "I2C-SDA/SPI_MOSI_C1") (pintype "bidirectional"))
    )
    (net (code "66") (name "unconnected-(U2-LORA_ANT-PadG2)") (class "Default")
      (node (ref "U2") (pin "G2") (pinfunction "LORA_ANT_G2") (pintype "bidirectional"))
    )
    (net (code "67") (name "unconnected-(U2-NFC1-PadD5)") (class "Default")
      (node (ref "U2") (pin "D5") (pinfunction "NFC1_D5") (pintype "bidirectional"))
    )
    (net (code "68") (name "unconnected-(U2-NFC2-PadB5)") (class "Default")
      (node (ref "U2") (pin "B5") (pinfunction "NFC2_B5") (pintype "bidirectional"))
    )
    (net (code "69") (name "unconnected-(U2-SPI-SCK-PadB2)") (class "Default")
      (node (ref "U2") (pin "B2") (pinfunction "SPI-SCK_B2") (pintype "bidirectional"))
    )
    (net (code "70") (name "unconnected-(U2-SWCLK-PadB4)") (class "Default")
      (node (ref "U2") (pin "B4") (pinfunction "SWCLK_B4") (pintype "bidirectional"))
    )
    (net (code "71") (name "unconnected-(U2-SWDIO-PadC4)") (class "Default")
      (node (ref "U2") (pin "C4") (pinfunction "SWDIO_C4") (pintype "bidirectional"))
    )
    (net (code "72") (name "unconnected-(U4-1PPS-Pad21)") (class "Default")
      (node (ref "U4") (pin "21") (pinfunction "1PPS_21") (pintype "bidirectional"))
    )
    (net (code "73") (name "unconnected-(U4-CLK-Pad18)") (class "Default")
      (node (ref "U4") (pin "18") (pinfunction "CLK_18") (pintype "bidirectional"))
    )
    (net (code "74") (name "unconnected-(U4-CS-Pad23)") (class "Default")
      (node (ref "U4") (pin "23") (pinfunction "CS_23") (pintype "bidirectional"))
    )
    (net (code "75") (name "unconnected-(U4-EX_ANT-Pad2)") (class "Default")
      (node (ref "U4") (pin "2") (pinfunction "EX_ANT_2") (pintype "bidirectional"))
    )
    (net (code "76") (name "unconnected-(U4-I2C_SCL-Pad14)") (class "Default")
      (node (ref "U4") (pin "14") (pinfunction "I2C_SCL_14") (pintype "bidirectional"))
    )
    (net (code "77") (name "unconnected-(U4-I2C_SDA-Pad13)") (class "Default")
      (node (ref "U4") (pin "13") (pinfunction "I2C_SDA_13") (pintype "bidirectional"))
    )
    (net (code "78") (name "unconnected-(U4-INT-Pad16)") (class "Default")
      (node (ref "U4") (pin "16") (pinfunction "INT_16") (pintype "bidirectional"))
    )
    (net (code "79") (name "unconnected-(U4-MISO-Pad15)") (class "Default")
      (node (ref "U4") (pin "15") (pinfunction "MISO_15") (pintype "bidirectional"))
    )
    (net (code "80") (name "unconnected-(U4-MOSI-Pad17)") (class "Default")
      (node (ref "U4") (pin "17") (pinfunction "MOSI_17") (pintype "bidirectional"))
    )
    (net (code "81") (name "unconnected-(U4-NRESET-Pad22)") (class "Default")
      (node (ref "U4") (pin "22") (pinfunction "NRESET_22") (pintype "bidirectional"))
    )
    (net (code "82") (name "unconnected-(U4-VCC-Pad7)") (class "Default")
      (node (ref "U4") (pin "7") (pinfunction "VCC_7") (pintype "bidirectional"))
    )
    (net (code "83") (name "unconnected-(U4-V_BACKUP-Pad8)") (class "Default")
      (node (ref "U4") (pin "8") (pinfunction "V_BACKUP_8") (pintype "bidirectional"))
    )
    (net (code "84") (name "unconnected-(U4-WAKEUP-Pad12)") (class "Default")
      (node (ref "U4") (pin "12") (pinfunction "WAKEUP_12") (pintype "bidirectional"))
    )
  )
)
